# Sheet4.net
KiCad netlist of a schematic drawn in Altium Designer
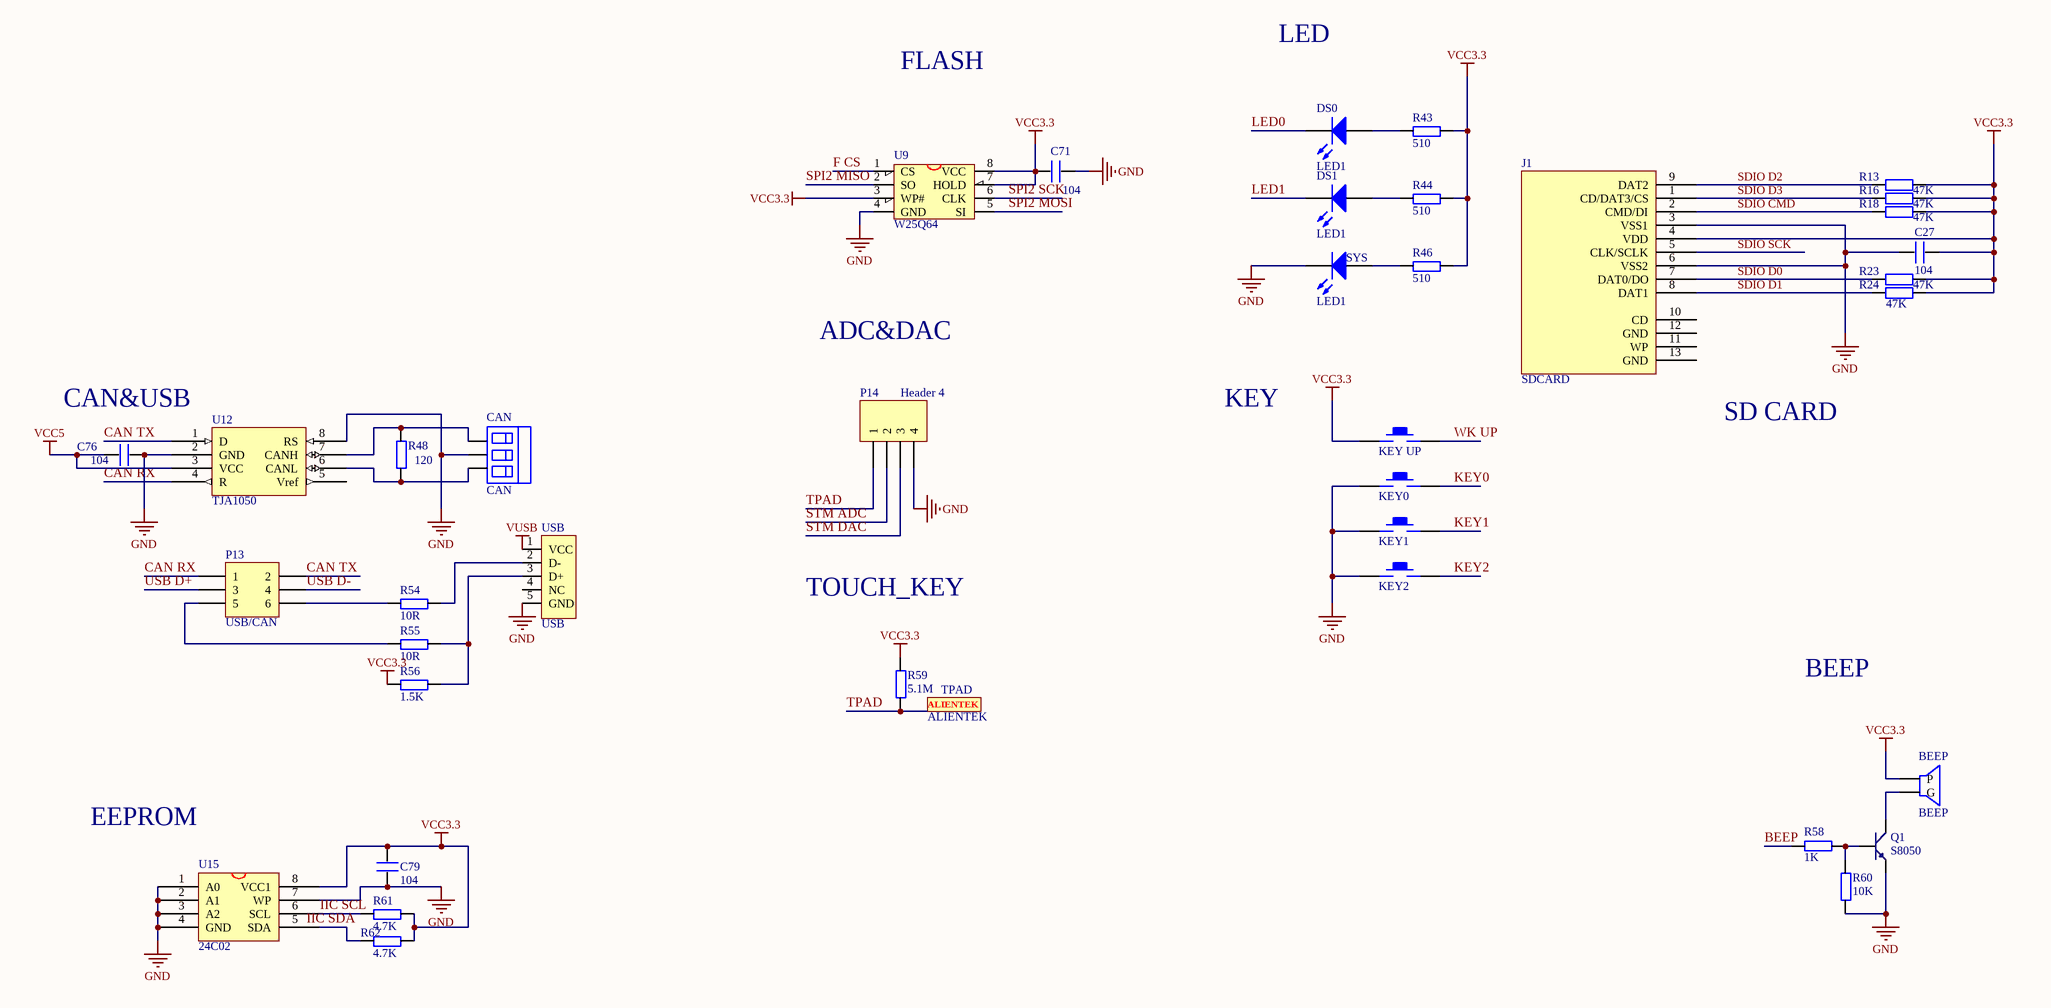
[diagram p0: Sheet4.SchDoc]

(export (version "E")
  (design (tool "Eeschema 10.0.6"))
  (components
    (comp (ref "BEEP") (value "BEEP") (footprint "BELL-5") (libsource (lib "战舰STM32开发板底板封装库") (part "BEEP")))
    (comp (ref "C27") (value "104") (footprint "0603P") (libsource (lib "液晶模块封装库") (part "C")))
    (comp (ref "C71") (value "104") (footprint "0603P") (libsource (lib "战舰STM32开发板底板封装库") (part "C")))
    (comp (ref "C76") (value "104") (footprint "0603P") (libsource (lib "战舰STM32开发板底板封装库") (part "C")))
    (comp (ref "C79") (value "104") (footprint "0603P") (libsource (lib "战舰STM32开发板底板封装库") (part "C")))
    (comp (ref "CAN")
      (value "CAN")
      (footprint "MKDSN_3RMI")
      (libsource (lib "战舰STM32开发板底板封装库") (part "HEAD3"))
    )
    (comp (ref "DS0")
      (value "LED1")
      (footprint "SMDLED")
      (description "Typical RED, GREEN, YELLOW, AMBER GaAs LED")
      (fields (field (name "PUBLISHER") "Altium Limited"))
      (libsource (lib "战舰STM32开发板底板封装库") (part "LED2"))
    )
    (comp (ref "DS1")
      (value "LED1")
      (footprint "SMDLED")
      (description "Typical RED, GREEN, YELLOW, AMBER GaAs LED")
      (fields (field (name "PUBLISHER") "Altium Limited"))
      (libsource (lib "战舰STM32开发板底板封装库") (part "LED2"))
    )
    (comp (ref "J1")
      (value "SDCARD")
      (footprint "SDCARD_L")
      (description "SD卡自弹")
      (libsource (lib "founder") (part "SDCARD"))
    )
    (comp (ref "KEY UP")
      (value "KEY_M")
      (footprint "KEY_M")
      (libsource (lib "战舰STM32开发板底板封装库") (part "KEY_M"))
    )
    (comp (ref "KEY0") (value "KEY_M") (footprint "KEY_M") (libsource (lib "战舰STM32开发板底板封装库") (part "KEY_M")))
    (comp (ref "KEY1") (value "KEY_M") (footprint "KEY_M") (libsource (lib "战舰STM32开发板底板封装库") (part "KEY_M")))
    (comp (ref "KEY2") (value "KEY_M") (footprint "KEY_M") (libsource (lib "战舰STM32开发板底板封装库") (part "KEY_M")))
    (comp (ref "P13")
      (value "USB/CAN")
      (footprint "HDR2X3")
      (description "Header, 3-Pin, Dual row")
      (fields (field (name "PUBLISHER") "Altium Limited"))
      (libsource (lib "战舰STM32开发板底板封装库") (part "Header 3X2"))
    )
    (comp (ref "P14")
      (value "Header 4")
      (footprint "HDR1X4")
      (description "Header, 4-Pin")
      (fields (field (name "PUBLISHER") "Altium Limited"))
      (libsource (lib "战舰STM32开发板底板封装库") (part "Header 4"))
    )
    (comp (ref "Q1")
      (value "S8050")
      (footprint "SOT-23R")
      (description "8050/BCW846/BCW847")
      (libsource (lib "战舰STM32开发板底板封装库") (part "NPN"))
    )
    (comp (ref "R13")
      (value "47K")
      (footprint "0603-1")
      (description "贴片电阻")
      (fields (field (name "Comment") "Res1") (field (name "PUBLISHER") "Altium Limited"))
      (libsource (lib "founder") (part "Res1"))
    )
    (comp (ref "R16")
      (value "47K")
      (footprint "0603-1")
      (description "贴片电阻")
      (fields (field (name "Comment") "Res1") (field (name "PUBLISHER") "Altium Limited"))
      (libsource (lib "founder") (part "Res1"))
    )
    (comp (ref "R18")
      (value "47K")
      (footprint "0603-1")
      (description "贴片电阻")
      (fields (field (name "Comment") "Res1") (field (name "PUBLISHER") "Altium Limited"))
      (libsource (lib "founder") (part "Res1"))
    )
    (comp (ref "R23")
      (value "47K")
      (footprint "0603-1")
      (description "贴片电阻")
      (fields (field (name "Comment") "Res1") (field (name "PUBLISHER") "Altium Limited"))
      (libsource (lib "founder") (part "Res1"))
    )
    (comp (ref "R24")
      (value "47K")
      (footprint "0603-1")
      (description "贴片电阻")
      (fields (field (name "Comment") "Res1") (field (name "PUBLISHER") "Altium Limited"))
      (libsource (lib "founder") (part "Res1"))
    )
    (comp (ref "R43") (value "510") (footprint "0603P") (libsource (lib "战舰STM32开发板底板封装库") (part "R")))
    (comp (ref "R44") (value "510") (footprint "0603P") (libsource (lib "战舰STM32开发板底板封装库") (part "R")))
    (comp (ref "R46") (value "510") (footprint "0603P") (libsource (lib "战舰STM32开发板底板封装库") (part "R")))
    (comp (ref "R48") (value "120") (footprint "0603P") (libsource (lib "战舰STM32开发板底板封装库") (part "R")))
    (comp (ref "R54") (value "10R") (footprint "0603P") (libsource (lib "战舰STM32开发板底板封装库") (part "R")))
    (comp (ref "R55") (value "10R") (footprint "0603P") (libsource (lib "战舰STM32开发板底板封装库") (part "R")))
    (comp (ref "R56") (value "1.5K") (footprint "0603P") (libsource (lib "战舰STM32开发板底板封装库") (part "R")))
    (comp (ref "R58") (value "1K") (footprint "0603P") (libsource (lib "战舰STM32开发板底板封装库") (part "R")))
    (comp (ref "R59") (value "5.1M") (footprint "0603P") (libsource (lib "战舰STM32开发板底板封装库") (part "R")))
    (comp (ref "R60") (value "10K") (footprint "0603P") (libsource (lib "战舰STM32开发板底板封装库") (part "R")))
    (comp (ref "R61") (value "4.7K") (footprint "0603P") (libsource (lib "战舰STM32开发板底板封装库") (part "R")))
    (comp (ref "R62") (value "4.7K") (footprint "0603P") (libsource (lib "战舰STM32开发板底板封装库") (part "R")))
    (comp (ref "SYS")
      (value "LED1")
      (footprint "SMDLED")
      (description "Typical RED, GREEN, YELLOW, AMBER GaAs LED")
      (fields (field (name "PUBLISHER") "Altium Limited"))
      (libsource (lib "战舰STM32开发板底板封装库") (part "LED2"))
    )
    (comp (ref "TPAD")
      (value "ALIENTEK")
      (footprint "ALIENTEK_PAD")
      (libsource (lib "战舰STM32开发板底板封装库") (part "ALIENTEK"))
    )
    (comp (ref "U9")
      (value "W25Q64")
      (footprint "SOIC-8")
      (description "W25X16;SST25VF016;MX25L1605")
      (libsource (lib "战舰STM32开发板底板封装库") (part "W25X16"))
    )
    (comp (ref "U12")
      (value "TJA1050")
      (footprint "SOP-8")
      (libsource (lib "战舰STM32开发板底板封装库") (part "SN65HVD230D"))
    )
    (comp (ref "U15") (value "24C02") (footprint "SOP-8") (libsource (lib "战舰STM32开发板底板封装库") (part "24C256")))
    (comp (ref "USB")
      (value "USB")
      (footprint "USB/SM0.8-6H5")
      (libsource (lib "战舰STM32开发板底板封装库") (part "USB5"))
    )
  )
  (nets
    (net (code "1") (name "/BEEP") (class "Default") (node (ref "R58") (pin "2") (pintype "passive")))
    (net (code "2") (name "/CAN RX") (class "Default")
      (node (ref "P13") (pin "1") (pinfunction "1_1") (pintype "passive"))
      (node (ref "U12") (pin "4") (pinfunction "R_4") (pintype "output"))
    )
    (net (code "3") (name "/CAN TX") (class "Default")
      (node (ref "P13") (pin "2") (pinfunction "2_2") (pintype "passive"))
      (node (ref "U12") (pin "1") (pinfunction "D_1") (pintype "input"))
    )
    (net (code "4") (name "/F CS") (class "Default")
      (node (ref "U9") (pin "1") (pinfunction "CS_1") (pintype "passive"))
    )
    (net (code "5") (name "/IIC SCL") (class "Default")
      (node (ref "R61") (pin "1") (pintype "passive"))
      (node (ref "U15") (pin "6") (pinfunction "SCL_6") (pintype "passive"))
    )
    (net (code "7") (name "/KEY0") (class "Default")
      (node (ref "KEY0") (pin "2") (pinfunction "2_2") (pintype "passive"))
    )
    (net (code "8") (name "/KEY1") (class "Default")
      (node (ref "KEY1") (pin "2") (pinfunction "2_2") (pintype "passive"))
    )
    (net (code "9") (name "/KEY2") (class "Default")
      (node (ref "KEY2") (pin "2") (pinfunction "2_2") (pintype "passive"))
    )
    (net (code "10") (name "/LED0") (class "Default")
      (node (ref "DS0") (pin "2") (pinfunction "K_2") (pintype "passive"))
    )
    (net (code "11") (name "/LED1") (class "Default")
      (node (ref "DS1") (pin "2") (pinfunction "K_2") (pintype "passive"))
    )
    (net (code "12") (name "/SDIO CMD") (class "Default")
      (node (ref "J1") (pin "2") (pinfunction "CMD/DI_2") (pintype "passive"))
      (node (ref "R18") (pin "1") (pinfunction "1_1") (pintype "passive"))
    )
    (net (code "13") (name "/SDIO D0") (class "Default")
      (node (ref "J1") (pin "7") (pinfunction "DAT0/DO_7") (pintype "passive"))
      (node (ref "R23") (pin "1") (pinfunction "1_1") (pintype "passive"))
    )
    (net (code "14") (name "/SDIO D1") (class "Default")
      (node (ref "J1") (pin "8") (pinfunction "DAT1_8") (pintype "passive"))
      (node (ref "R24") (pin "1") (pinfunction "1_1") (pintype "passive"))
    )
    (net (code "15") (name "/SDIO D2") (class "Default")
      (node (ref "J1") (pin "9") (pinfunction "DAT2_9") (pintype "passive"))
      (node (ref "R13") (pin "1") (pinfunction "1_1") (pintype "passive"))
    )
    (net (code "16") (name "/SDIO D3") (class "Default")
      (node (ref "J1") (pin "1") (pinfunction "CD/DAT3/CS_1") (pintype "passive"))
      (node (ref "R16") (pin "1") (pinfunction "1_1") (pintype "passive"))
    )
    (net (code "17") (name "/SDIO SCK") (class "Default")
      (node (ref "J1") (pin "5") (pinfunction "CLK/SCLK_5") (pintype "passive"))
    )
    (net (code "18") (name "/SPI2 MISO") (class "Default")
      (node (ref "U9") (pin "2") (pinfunction "SO_2") (pintype "passive"))
    )
    (net (code "19") (name "/SPI2 MOSI") (class "Default")
      (node (ref "U9") (pin "5") (pinfunction "SI_5") (pintype "passive"))
    )
    (net (code "20") (name "/SPI2 SCK") (class "Default")
      (node (ref "U9") (pin "6") (pinfunction "CLK_6") (pintype "passive"))
    )
    (net (code "21") (name "/STM ADC") (class "Default")
      (node (ref "P14") (pin "2") (pinfunction "2_2") (pintype "passive"))
    )
    (net (code "22") (name "/STM DAC") (class "Default")
      (node (ref "P14") (pin "3") (pinfunction "3_3") (pintype "passive"))
    )
    (net (code "23") (name "/TPAD") (class "Default")
      (node (ref "P14") (pin "1") (pinfunction "1_1") (pintype "passive"))
      (node (ref "R59") (pin "1") (pintype "passive"))
    )
    (net (code "24") (name "/USB D+") (class "Default")
      (node (ref "P13") (pin "3") (pinfunction "3_3") (pintype "passive"))
    )
    (net (code "25") (name "/USB D-") (class "Default")
      (node (ref "P13") (pin "4") (pinfunction "4_4") (pintype "passive"))
    )
    (net (code "26") (name "/WK UP") (class "Default")
      (node (ref "KEY UP") (pin "2") (pinfunction "2_2") (pintype "passive"))
    )
    (net (code "27") (name "GND") (class "Default")
      (node (ref "C27") (pin "1") (pintype "passive"))
      (node (ref "C71") (pin "2") (pintype "passive"))
      (node (ref "C76") (pin "2") (pintype "passive"))
      (node (ref "C79") (pin "1") (pintype "passive"))
      (node (ref "CAN") (pin "2") (pinfunction "2_2") (pintype "passive"))
      (node (ref "J1") (pin "3") (pinfunction "VSS1_3") (pintype "passive"))
      (node (ref "J1") (pin "6") (pinfunction "VSS2_6") (pintype "passive"))
      (node (ref "KEY0") (pin "1") (pinfunction "1_1") (pintype "passive"))
      (node (ref "KEY1") (pin "1") (pinfunction "1_1") (pintype "passive"))
      (node (ref "KEY2") (pin "1") (pinfunction "1_1") (pintype "passive"))
      (node (ref "P14") (pin "4") (pinfunction "4_4") (pintype "passive"))
      (node (ref "Q1") (pin "1") (pinfunction "E_1") (pintype "passive"))
      (node (ref "R60") (pin "1") (pintype "passive"))
      (node (ref "SYS") (pin "2") (pinfunction "K_2") (pintype "passive"))
      (node (ref "U12") (pin "2") (pinfunction "GND_2") (pintype "power_in"))
      (node (ref "U12") (pin "8") (pinfunction "RS_8") (pintype "input"))
      (node (ref "U15") (pin "1") (pinfunction "A0_1") (pintype "passive"))
      (node (ref "U15") (pin "2") (pinfunction "A1_2") (pintype "passive"))
      (node (ref "U15") (pin "3") (pinfunction "A2_3") (pintype "passive"))
      (node (ref "U15") (pin "4") (pinfunction "GND_4") (pintype "passive"))
      (node (ref "U15") (pin "7") (pinfunction "WP_7") (pintype "passive"))
      (node (ref "U9") (pin "4") (pinfunction "GND_4") (pintype "passive"))
      (node (ref "USB") (pin "5") (pinfunction "GND_5") (pintype "passive"))
    )
    (net (code "28") (name "Net-(BEEP-G)") (class "Default")
      (node (ref "BEEP") (pin "2") (pinfunction "G_2") (pintype "passive"))
      (node (ref "Q1") (pin "3") (pinfunction "C_3") (pintype "passive"))
    )
    (net (code "29") (name "Net-(DS0-A)") (class "Default")
      (node (ref "DS0") (pin "1") (pinfunction "A_1") (pintype "passive"))
      (node (ref "R43") (pin "1") (pintype "passive"))
    )
    (net (code "30") (name "Net-(DS1-A)") (class "Default")
      (node (ref "DS1") (pin "1") (pinfunction "A_1") (pintype "passive"))
      (node (ref "R44") (pin "1") (pintype "passive"))
    )
    (net (code "31") (name "Net-(P13-Pad5)") (class "Default")
      (node (ref "P13") (pin "5") (pinfunction "5_5") (pintype "passive"))
      (node (ref "R55") (pin "1") (pintype "passive"))
    )
    (net (code "32") (name "Net-(P13-Pad6)") (class "Default")
      (node (ref "P13") (pin "6") (pinfunction "6_6") (pintype "passive"))
      (node (ref "R54") (pin "1") (pintype "passive"))
    )
    (net (code "33") (name "Net-(Q1-B)") (class "Default")
      (node (ref "Q1") (pin "2") (pinfunction "B_2") (pintype "passive"))
      (node (ref "R58") (pin "1") (pintype "passive"))
      (node (ref "R60") (pin "2") (pintype "passive"))
    )
    (net (code "34") (name "Net-(SYS-A)") (class "Default")
      (node (ref "R46") (pin "1") (pintype "passive"))
      (node (ref "SYS") (pin "1") (pinfunction "A_1") (pintype "passive"))
    )
    (net (code "35") (name "Net-(U12-CANH)") (class "Default")
      (node (ref "CAN") (pin "1") (pinfunction "1_1") (pintype "passive"))
      (node (ref "R48") (pin "2") (pintype "passive"))
      (node (ref "U12") (pin "7") (pinfunction "CANH_7") (pintype "bidirectional"))
    )
    (net (code "36") (name "Net-(U12-CANL)") (class "Default")
      (node (ref "CAN") (pin "3") (pinfunction "3_3") (pintype "passive"))
      (node (ref "R48") (pin "1") (pintype "passive"))
      (node (ref "U12") (pin "6") (pinfunction "CANL_6") (pintype "bidirectional"))
    )
    (net (code "37") (name "Net-(U15-SDA)") (class "Default")
      (node (ref "R62") (pin "1") (pintype "passive"))
      (node (ref "U15") (pin "5") (pinfunction "SDA_5") (pintype "passive"))
    )
    (net (code "38") (name "Net-(USB-D+)") (class "Default")
      (node (ref "R55") (pin "2") (pintype "passive"))
      (node (ref "R56") (pin "2") (pintype "passive"))
      (node (ref "USB") (pin "3") (pinfunction "D+_3") (pintype "passive"))
    )
    (net (code "39") (name "Net-(USB-D-)") (class "Default")
      (node (ref "R54") (pin "2") (pintype "passive"))
      (node (ref "USB") (pin "2") (pinfunction "D-_2") (pintype "passive"))
    )
    (net (code "40") (name "VCC3.3") (class "Default")
      (node (ref "BEEP") (pin "1") (pinfunction "P_1") (pintype "passive"))
      (node (ref "C27") (pin "2") (pintype "passive"))
      (node (ref "C71") (pin "1") (pintype "passive"))
      (node (ref "C79") (pin "2") (pintype "passive"))
      (node (ref "J1") (pin "4") (pinfunction "VDD_4") (pintype "passive"))
      (node (ref "KEY UP") (pin "1") (pinfunction "1_1") (pintype "passive"))
      (node (ref "R13") (pin "2") (pinfunction "2_2") (pintype "passive"))
      (node (ref "R16") (pin "2") (pinfunction "2_2") (pintype "passive"))
      (node (ref "R18") (pin "2") (pinfunction "2_2") (pintype "passive"))
      (node (ref "R23") (pin "2") (pinfunction "2_2") (pintype "passive"))
      (node (ref "R24") (pin "2") (pinfunction "2_2") (pintype "passive"))
      (node (ref "R43") (pin "2") (pintype "passive"))
      (node (ref "R44") (pin "2") (pintype "passive"))
      (node (ref "R46") (pin "2") (pintype "passive"))
      (node (ref "R56") (pin "1") (pintype "passive"))
      (node (ref "R59") (pin "2") (pintype "passive"))
      (node (ref "R61") (pin "2") (pintype "passive"))
      (node (ref "R62") (pin "2") (pintype "passive"))
      (node (ref "U15") (pin "8") (pinfunction "VCC1_8") (pintype "passive"))
      (node (ref "U9") (pin "3") (pinfunction "WP#_3") (pintype "passive"))
      (node (ref "U9") (pin "7") (pinfunction "HOLD_7") (pintype "passive"))
      (node (ref "U9") (pin "8") (pinfunction "VCC_8") (pintype "passive"))
    )
    (net (code "41") (name "VCC5") (class "Default")
      (node (ref "C76") (pin "1") (pintype "passive"))
      (node (ref "U12") (pin "3") (pinfunction "VCC_3") (pintype "power_in"))
    )
    (net (code "42") (name "VUSB") (class "Default")
      (node (ref "USB") (pin "1") (pinfunction "VCC_1") (pintype "passive"))
    )
    (net (code "43") (name "unconnected-(J1-CD-Pad10)") (class "Default")
      (node (ref "J1") (pin "10") (pinfunction "CD_10") (pintype "passive"))
    )
    (net (code "44") (name "unconnected-(J1-GND-Pad12)") (class "Default")
      (node (ref "J1") (pin "12") (pinfunction "GND_12") (pintype "passive"))
    )
    (net (code "45") (name "unconnected-(J1-GND-Pad13)") (class "Default")
      (node (ref "J1") (pin "13") (pinfunction "GND_13") (pintype "passive"))
    )
    (net (code "46") (name "unconnected-(J1-WP-Pad11)") (class "Default")
      (node (ref "J1") (pin "11") (pinfunction "WP_11") (pintype "passive"))
    )
    (net (code "47") (name "unconnected-(U12-Vref-Pad5)") (class "Default")
      (node (ref "U12") (pin "5") (pinfunction "Vref_5") (pintype "output"))
    )
    (net (code "48") (name "unconnected-(USB-NC-Pad4)") (class "Default")
      (node (ref "USB") (pin "4") (pinfunction "NC_4") (pintype "passive"))
    )
  )
)
